# Amplifier.net
KiCad netlist of a schematic drawn in Altium Designer
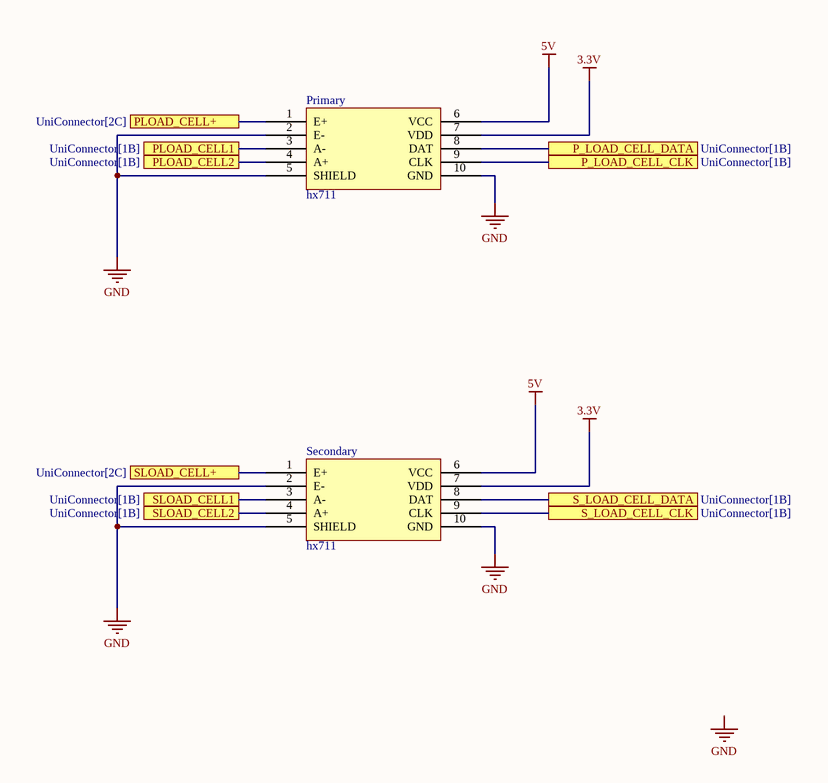
[diagram p0: Amplifier.SchDoc]

(export (version "E")
  (design (tool "Eeschema 10.0.6"))
  (components
    (comp (ref "Primary")
      (value "hx711")
      (footprint "PCBComponent_1")
      (libsource (lib "HX711LIB") (part "Component_1"))
    )
    (comp (ref "Secondary")
      (value "hx711")
      (footprint "PCBComponent_1")
      (libsource (lib "HX711LIB") (part "Component_1"))
    )
  )
  (nets
    (net (code "1") (name "/PLOAD_CELL+") (class "Default")
      (node (ref "Primary") (pin "1") (pinfunction "E+_1") (pintype "passive"))
    )
    (net (code "2") (name "/PLOAD_CELL1") (class "Default")
      (node (ref "Primary") (pin "3") (pinfunction "A-_3") (pintype "passive"))
    )
    (net (code "3") (name "/PLOAD_CELL2") (class "Default")
      (node (ref "Primary") (pin "4") (pinfunction "A+_4") (pintype "passive"))
    )
    (net (code "4") (name "/P_LOAD_CELL_CLK") (class "Default")
      (node (ref "Primary") (pin "9") (pinfunction "CLK_9") (pintype "passive"))
    )
    (net (code "5") (name "/P_LOAD_CELL_DATA") (class "Default")
      (node (ref "Primary") (pin "8") (pinfunction "DAT_8") (pintype "passive"))
    )
    (net (code "6") (name "/SLOAD_CELL+") (class "Default")
      (node (ref "Secondary") (pin "1") (pinfunction "E+_1") (pintype "passive"))
    )
    (net (code "7") (name "/SLOAD_CELL1") (class "Default")
      (node (ref "Secondary") (pin "3") (pinfunction "A-_3") (pintype "passive"))
    )
    (net (code "8") (name "/SLOAD_CELL2") (class "Default")
      (node (ref "Secondary") (pin "4") (pinfunction "A+_4") (pintype "passive"))
    )
    (net (code "9") (name "/S_LOAD_CELL_CLK") (class "Default")
      (node (ref "Secondary") (pin "9") (pinfunction "CLK_9") (pintype "passive"))
    )
    (net (code "10") (name "/S_LOAD_CELL_DATA") (class "Default")
      (node (ref "Secondary") (pin "8") (pinfunction "DAT_8") (pintype "passive"))
    )
    (net (code "11") (name "3.3V") (class "Default")
      (node (ref "Primary") (pin "7") (pinfunction "VDD_7") (pintype "passive"))
      (node (ref "Secondary") (pin "7") (pinfunction "VDD_7") (pintype "passive"))
    )
    (net (code "12") (name "5V") (class "Default")
      (node (ref "Primary") (pin "6") (pinfunction "VCC_6") (pintype "passive"))
      (node (ref "Secondary") (pin "6") (pinfunction "VCC_6") (pintype "passive"))
    )
    (net (code "13") (name "GND") (class "Default")
      (node (ref "Primary") (pin "10") (pinfunction "GND_10") (pintype "passive"))
      (node (ref "Primary") (pin "2") (pinfunction "E-_2") (pintype "passive"))
      (node (ref "Primary") (pin "5") (pinfunction "SHIELD_5") (pintype "passive"))
      (node (ref "Secondary") (pin "10") (pinfunction "GND_10") (pintype "passive"))
      (node (ref "Secondary") (pin "2") (pinfunction "E-_2") (pintype "passive"))
      (node (ref "Secondary") (pin "5") (pinfunction "SHIELD_5") (pintype "passive"))
    )
  )
)
